# IO_Connectors.net
KiCad netlist of a schematic drawn in Altium Designer
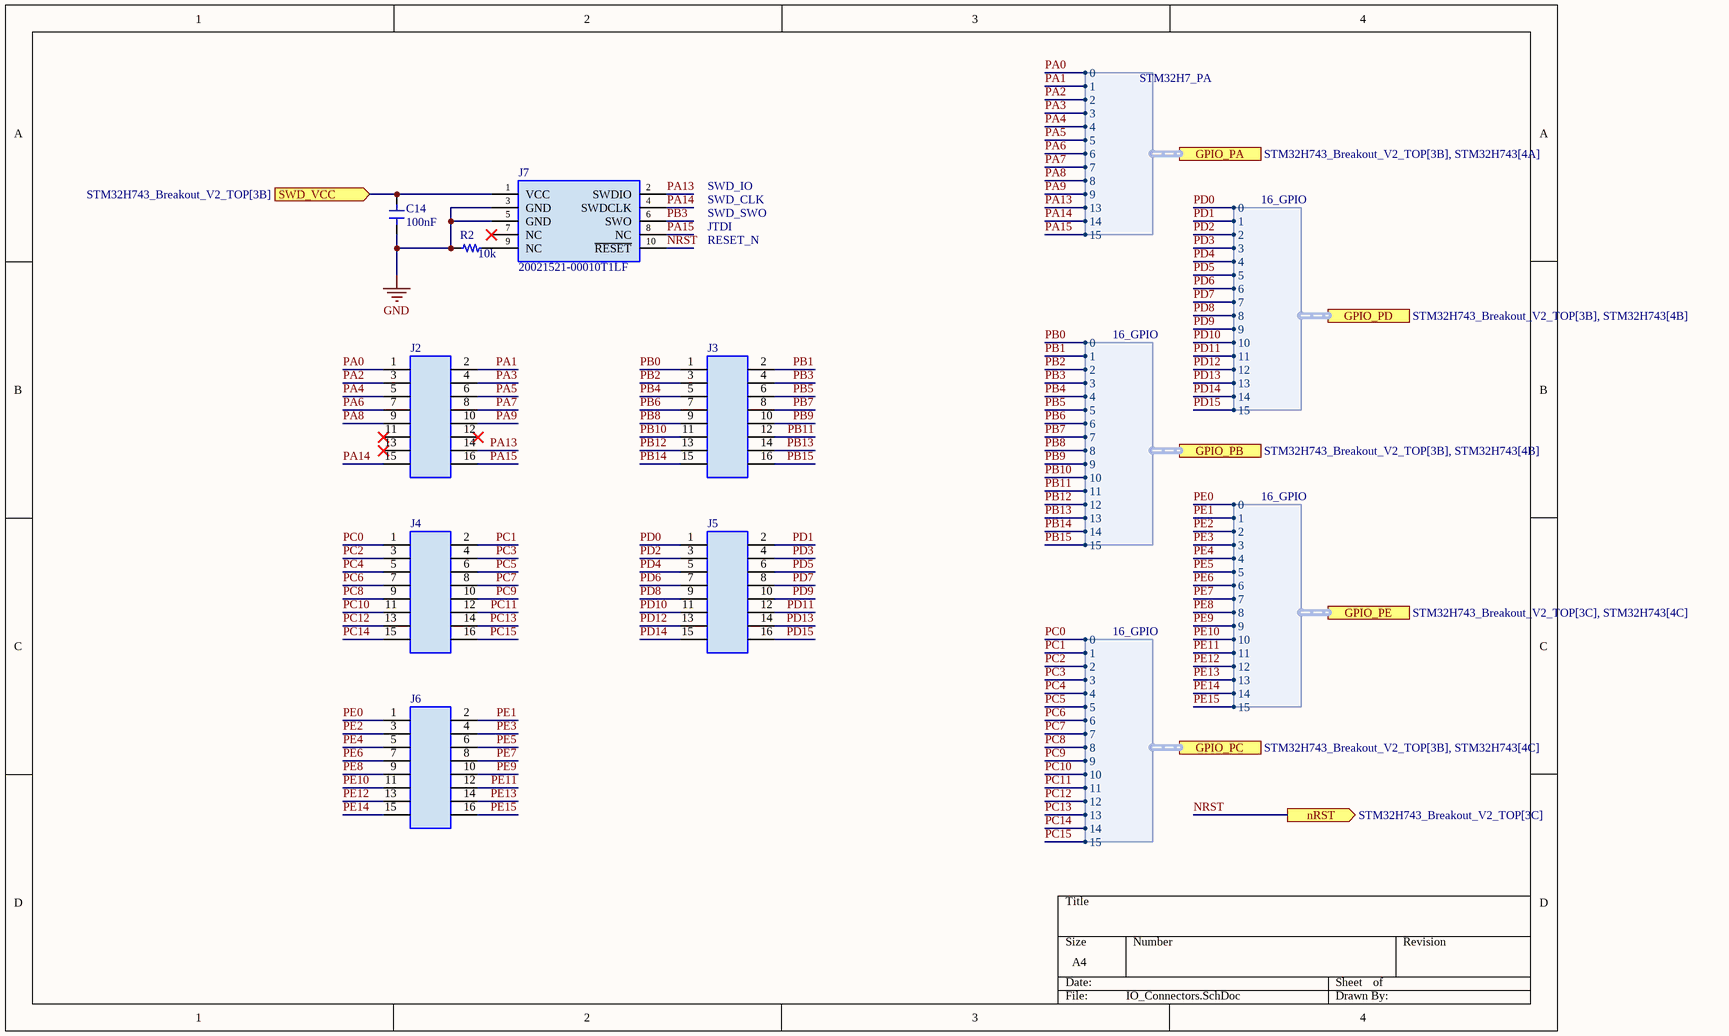
[diagram p0: IO_Connectors.SchDoc]

(export (version "E")
  (design (tool "Eeschema 10.0.6"))
  (components
    (comp (ref "C14")
      (value "C 0603 100nF 10% 50V X7R")
      (footprint "C-0603")
      (description "SMD Capacitor, Ceramic")
      (fields
        (field (name "CAPACITANCE") "100nF")
        (field (name "VOLTAGE") "50V")
        (field (name "TOLERANCE") "10%")
      )
      (libsource (lib "Project Rapid - Bruin Space") (part "Capacitor-NP"))
    )
    (comp (ref "J2")
      (value "SULLINS_PPPC082LFBN-RC")
      (footprint "2.54_08x02_female_header")
      (description "2.54mm pitch 8x2 female pin header")
      (libsource (lib "Project Rapid - Bruin Space") (part "header-8x2"))
    )
    (comp (ref "J3")
      (value "SULLINS_PPPC082LFBN-RC")
      (footprint "2.54_08x02_female_header")
      (description "2.54mm pitch 8x2 female pin header")
      (libsource (lib "Project Rapid - Bruin Space") (part "header-8x2"))
    )
    (comp (ref "J4")
      (value "SULLINS_PPPC082LFBN-RC")
      (footprint "2.54_08x02_female_header")
      (description "2.54mm pitch 8x2 female pin header")
      (libsource (lib "Project Rapid - Bruin Space") (part "header-8x2"))
    )
    (comp (ref "J5")
      (value "SULLINS_PPPC082LFBN-RC")
      (footprint "2.54_08x02_female_header")
      (description "2.54mm pitch 8x2 female pin header")
      (libsource (lib "Project Rapid - Bruin Space") (part "header-8x2"))
    )
    (comp (ref "J6")
      (value "SULLINS_PPPC082LFBN-RC")
      (footprint "2.54_08x02_female_header")
      (description "2.54mm pitch 8x2 female pin header")
      (libsource (lib "Project Rapid - Bruin Space") (part "header-8x2"))
    )
    (comp (ref "J7")
      (value "20021521-00010T1LF")
      (footprint "20021521-00010T1LF")
      (description "1.27mm Pitch Micro Header, 2x5Pos SMD, Shrouded, SWD/JTAG")
      (libsource (lib "Project Rapid - Bruin Space") (part "Debug SWD ARM 2x5pin 1.27mm Pitch"))
    )
    (comp (ref "R2")
      (value "R 0603 100 1% 0.100W 100PPM")
      (footprint "R-0603")
      (description "SMD Resistor, Thick Film")
      (fields (field (name "RESISTANCE") "10k") (field (name "TOLERANCE") "1%"))
      (libsource (lib "Project Rapid - Bruin Space") (part "Resistor"))
    )
  )
  (nets
    (net (code "3") (name "/NRST") (class "Default")
      (node (ref "J7") (pin "10") (pinfunction "~{RESET}_10") (pintype "passive"))
    )
    (net (code "4") (name "/PA0") (class "Default") (node (ref "J2") (pin "1") (pintype "passive")))
    (net (code "5") (name "/PA1") (class "Default") (node (ref "J2") (pin "2") (pintype "passive")))
    (net (code "6") (name "/PA2") (class "Default") (node (ref "J2") (pin "3") (pintype "passive")))
    (net (code "7") (name "/PA3") (class "Default") (node (ref "J2") (pin "4") (pintype "passive")))
    (net (code "8") (name "/PA4") (class "Default") (node (ref "J2") (pin "5") (pintype "passive")))
    (net (code "9") (name "/PA5") (class "Default") (node (ref "J2") (pin "6") (pintype "passive")))
    (net (code "10") (name "/PA6") (class "Default") (node (ref "J2") (pin "7") (pintype "passive")))
    (net (code "11") (name "/PA7") (class "Default") (node (ref "J2") (pin "8") (pintype "passive")))
    (net (code "12") (name "/PA8") (class "Default") (node (ref "J2") (pin "9") (pintype "passive")))
    (net (code "13") (name "/PA9") (class "Default") (node (ref "J2") (pin "10") (pintype "passive")))
    (net (code "14") (name "/PA13") (class "Default")
      (node (ref "J2") (pin "14") (pintype "passive"))
      (node (ref "J7") (pin "2") (pinfunction "SWDIO_2") (pintype "passive"))
    )
    (net (code "15") (name "/PA14") (class "Default")
      (node (ref "J2") (pin "15") (pintype "passive"))
      (node (ref "J7") (pin "4") (pinfunction "SWDCLK_4") (pintype "passive"))
    )
    (net (code "16") (name "/PA15") (class "Default")
      (node (ref "J2") (pin "16") (pintype "passive"))
      (node (ref "J7") (pin "8") (pinfunction "NC_8") (pintype "passive"))
    )
    (net (code "17") (name "/PB0") (class "Default") (node (ref "J3") (pin "1") (pintype "passive")))
    (net (code "18") (name "/PB1") (class "Default") (node (ref "J3") (pin "2") (pintype "passive")))
    (net (code "19") (name "/PB2") (class "Default") (node (ref "J3") (pin "3") (pintype "passive")))
    (net (code "20") (name "/PB3") (class "Default")
      (node (ref "J3") (pin "4") (pintype "passive"))
      (node (ref "J7") (pin "6") (pinfunction "SWO_6") (pintype "passive"))
    )
    (net (code "21") (name "/PB4") (class "Default") (node (ref "J3") (pin "5") (pintype "passive")))
    (net (code "22") (name "/PB5") (class "Default") (node (ref "J3") (pin "6") (pintype "passive")))
    (net (code "23") (name "/PB6") (class "Default") (node (ref "J3") (pin "7") (pintype "passive")))
    (net (code "24") (name "/PB7") (class "Default") (node (ref "J3") (pin "8") (pintype "passive")))
    (net (code "25") (name "/PB8") (class "Default") (node (ref "J3") (pin "9") (pintype "passive")))
    (net (code "26") (name "/PB9") (class "Default") (node (ref "J3") (pin "10") (pintype "passive")))
    (net (code "27") (name "/PB10") (class "Default") (node (ref "J3") (pin "11") (pintype "passive")))
    (net (code "28") (name "/PB11") (class "Default") (node (ref "J3") (pin "12") (pintype "passive")))
    (net (code "29") (name "/PB12") (class "Default") (node (ref "J3") (pin "13") (pintype "passive")))
    (net (code "30") (name "/PB13") (class "Default") (node (ref "J3") (pin "14") (pintype "passive")))
    (net (code "31") (name "/PB14") (class "Default") (node (ref "J3") (pin "15") (pintype "passive")))
    (net (code "32") (name "/PB15") (class "Default") (node (ref "J3") (pin "16") (pintype "passive")))
    (net (code "33") (name "/PC0") (class "Default") (node (ref "J4") (pin "1") (pintype "passive")))
    (net (code "34") (name "/PC1") (class "Default") (node (ref "J4") (pin "2") (pintype "passive")))
    (net (code "35") (name "/PC2") (class "Default") (node (ref "J4") (pin "3") (pintype "passive")))
    (net (code "36") (name "/PC3") (class "Default") (node (ref "J4") (pin "4") (pintype "passive")))
    (net (code "37") (name "/PC4") (class "Default") (node (ref "J4") (pin "5") (pintype "passive")))
    (net (code "38") (name "/PC5") (class "Default") (node (ref "J4") (pin "6") (pintype "passive")))
    (net (code "39") (name "/PC6") (class "Default") (node (ref "J4") (pin "7") (pintype "passive")))
    (net (code "40") (name "/PC7") (class "Default") (node (ref "J4") (pin "8") (pintype "passive")))
    (net (code "41") (name "/PC8") (class "Default") (node (ref "J4") (pin "9") (pintype "passive")))
    (net (code "42") (name "/PC9") (class "Default") (node (ref "J4") (pin "10") (pintype "passive")))
    (net (code "43") (name "/PC10") (class "Default") (node (ref "J4") (pin "11") (pintype "passive")))
    (net (code "44") (name "/PC11") (class "Default") (node (ref "J4") (pin "12") (pintype "passive")))
    (net (code "45") (name "/PC12") (class "Default") (node (ref "J4") (pin "13") (pintype "passive")))
    (net (code "46") (name "/PC13") (class "Default") (node (ref "J4") (pin "14") (pintype "passive")))
    (net (code "47") (name "/PC14") (class "Default") (node (ref "J4") (pin "15") (pintype "passive")))
    (net (code "48") (name "/PC15") (class "Default") (node (ref "J4") (pin "16") (pintype "passive")))
    (net (code "49") (name "/PD0") (class "Default") (node (ref "J5") (pin "1") (pintype "passive")))
    (net (code "50") (name "/PD1") (class "Default") (node (ref "J5") (pin "2") (pintype "passive")))
    (net (code "51") (name "/PD2") (class "Default") (node (ref "J5") (pin "3") (pintype "passive")))
    (net (code "52") (name "/PD3") (class "Default") (node (ref "J5") (pin "4") (pintype "passive")))
    (net (code "53") (name "/PD4") (class "Default") (node (ref "J5") (pin "5") (pintype "passive")))
    (net (code "54") (name "/PD5") (class "Default") (node (ref "J5") (pin "6") (pintype "passive")))
    (net (code "55") (name "/PD6") (class "Default") (node (ref "J5") (pin "7") (pintype "passive")))
    (net (code "56") (name "/PD7") (class "Default") (node (ref "J5") (pin "8") (pintype "passive")))
    (net (code "57") (name "/PD8") (class "Default") (node (ref "J5") (pin "9") (pintype "passive")))
    (net (code "58") (name "/PD9") (class "Default") (node (ref "J5") (pin "10") (pintype "passive")))
    (net (code "59") (name "/PD10") (class "Default") (node (ref "J5") (pin "11") (pintype "passive")))
    (net (code "60") (name "/PD11") (class "Default") (node (ref "J5") (pin "12") (pintype "passive")))
    (net (code "61") (name "/PD12") (class "Default") (node (ref "J5") (pin "13") (pintype "passive")))
    (net (code "62") (name "/PD13") (class "Default") (node (ref "J5") (pin "14") (pintype "passive")))
    (net (code "63") (name "/PD14") (class "Default") (node (ref "J5") (pin "15") (pintype "passive")))
    (net (code "64") (name "/PD15") (class "Default") (node (ref "J5") (pin "16") (pintype "passive")))
    (net (code "65") (name "/PE0") (class "Default") (node (ref "J6") (pin "1") (pintype "passive")))
    (net (code "66") (name "/PE1") (class "Default") (node (ref "J6") (pin "2") (pintype "passive")))
    (net (code "67") (name "/PE2") (class "Default") (node (ref "J6") (pin "3") (pintype "passive")))
    (net (code "68") (name "/PE3") (class "Default") (node (ref "J6") (pin "4") (pintype "passive")))
    (net (code "69") (name "/PE4") (class "Default") (node (ref "J6") (pin "5") (pintype "passive")))
    (net (code "70") (name "/PE5") (class "Default") (node (ref "J6") (pin "6") (pintype "passive")))
    (net (code "71") (name "/PE6") (class "Default") (node (ref "J6") (pin "7") (pintype "passive")))
    (net (code "72") (name "/PE7") (class "Default") (node (ref "J6") (pin "8") (pintype "passive")))
    (net (code "73") (name "/PE8") (class "Default") (node (ref "J6") (pin "9") (pintype "passive")))
    (net (code "74") (name "/PE9") (class "Default") (node (ref "J6") (pin "10") (pintype "passive")))
    (net (code "75") (name "/PE10") (class "Default") (node (ref "J6") (pin "11") (pintype "passive")))
    (net (code "76") (name "/PE11") (class "Default") (node (ref "J6") (pin "12") (pintype "passive")))
    (net (code "77") (name "/PE12") (class "Default") (node (ref "J6") (pin "13") (pintype "passive")))
    (net (code "78") (name "/PE13") (class "Default") (node (ref "J6") (pin "14") (pintype "passive")))
    (net (code "79") (name "/PE14") (class "Default") (node (ref "J6") (pin "15") (pintype "passive")))
    (net (code "80") (name "/PE15") (class "Default") (node (ref "J6") (pin "16") (pintype "passive")))
    (net (code "81") (name "/SWD_VCC") (class "Default")
      (node (ref "C14") (pin "2") (pinfunction "2_2") (pintype "passive"))
      (node (ref "J7") (pin "1") (pinfunction "VCC_1") (pintype "passive"))
    )
    (net (code "84") (name "GND") (class "Default")
      (node (ref "C14") (pin "1") (pinfunction "1_1") (pintype "passive"))
      (node (ref "J7") (pin "3") (pinfunction "GND_3") (pintype "passive"))
      (node (ref "J7") (pin "5") (pinfunction "GND_5") (pintype "passive"))
      (node (ref "R2") (pin "1") (pinfunction "1_1") (pintype "passive"))
    )
    (net (code "85") (name "Net-(J7-NC-Pad9)") (class "Default")
      (node (ref "J7") (pin "9") (pinfunction "NC_9") (pintype "passive"))
      (node (ref "R2") (pin "2") (pinfunction "2_2") (pintype "passive"))
    )
    (net (code "86") (name "unconnected-(J2-Pad11)") (class "Default")
      (node (ref "J2") (pin "11") (pintype "passive+no_connect"))
    )
    (net (code "87") (name "unconnected-(J2-Pad12)") (class "Default")
      (node (ref "J2") (pin "12") (pintype "passive+no_connect"))
    )
    (net (code "88") (name "unconnected-(J2-Pad13)") (class "Default")
      (node (ref "J2") (pin "13") (pintype "passive+no_connect"))
    )
    (net (code "89") (name "unconnected-(J7-NC-Pad7)") (class "Default")
      (node (ref "J7") (pin "7") (pinfunction "NC_7") (pintype "passive+no_connect"))
    )
  )
)
